# BatteryMainSystem.net
KiCad netlist of a schematic drawn in Altium Designer
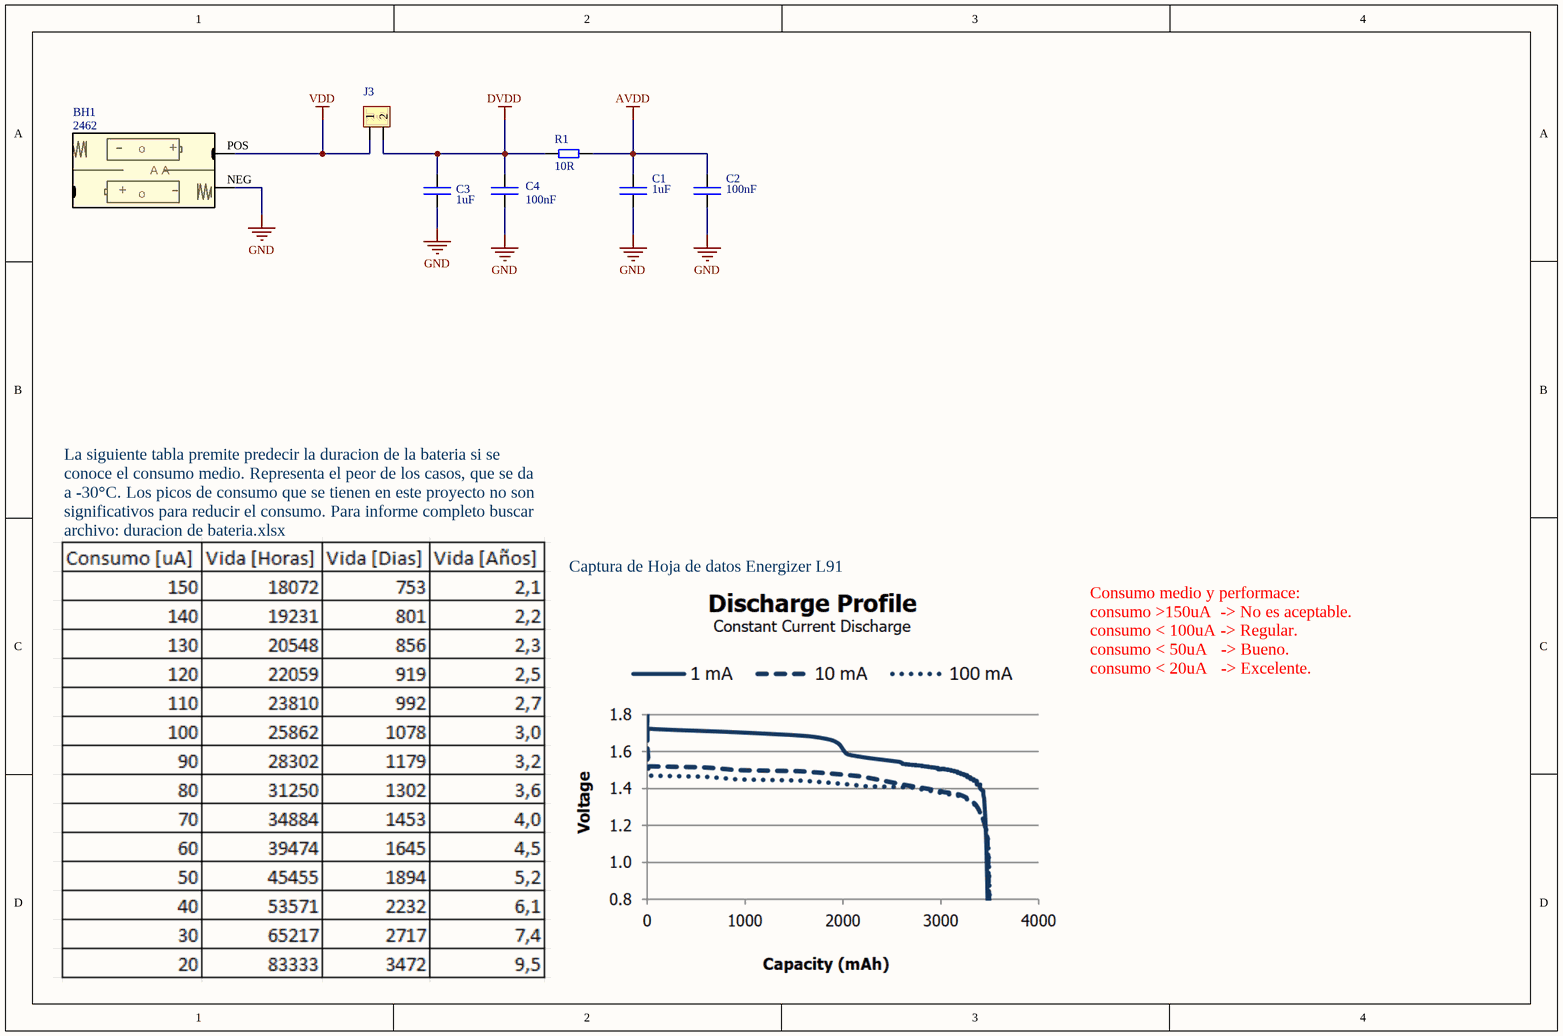
[diagram p0: BatteryMainSystem.SchDoc]

(export (version "E")
  (design (tool "Eeschema 10.0.6"))
  (components
    (comp (ref "BH1")
      (value "2462")
      (footprint "BATTERY_HOLDER_2XAA")
      (description "Battery holder 2XAA TH")
      (fields (field (name "MANUFACTURER") "Keystone"))
      (libsource (lib "flowmeet") (part "2462"))
    )
    (comp (ref "C1")
      (value "1uF")
      (footprint "CAP_SM0603_YAGEOCC2_N")
      (description "CAP 1uF SM0603 X7R 10V YAGEO CC2")
      (fields
        (field (name "MANUFACTURER") "Yageo")
        (field (name "MANUFACTURER PART NUMBER") "CC0603KRX7R6BB105")
      )
      (libsource (lib "yageo") (part "CC0603KRX7R6BB105"))
    )
    (comp (ref "C2")
      (value "100nF")
      (footprint "CAP_SM0603_YAGEOCC2_N")
      (description "CAP 100nF SM0603 X7R 50V YAGEO CC2")
      (fields
        (field (name "MANUFACTURER") "Yageo")
        (field (name "MANUFACTURER PART NUMBER") "CC0603KRX7R9BB104")
      )
      (libsource (lib "yageo") (part "CC0603KRX7R9BB104"))
    )
    (comp (ref "C3")
      (value "1uF")
      (footprint "CAP_SM0603_YAGEOCC2_N")
      (description "CAP 1uF SM0603 X7R 10V YAGEO CC2")
      (fields
        (field (name "MANUFACTURER") "Yageo")
        (field (name "MANUFACTURER PART NUMBER") "CC0603KRX7R6BB105")
      )
      (libsource (lib "yageo") (part "CC0603KRX7R6BB105"))
    )
    (comp (ref "C4")
      (value "100nF")
      (footprint "CAP_SM0603_YAGEOCC2_N")
      (description "CAP 100nF SM0603 X7R 50V YAGEO CC2")
      (fields
        (field (name "MANUFACTURER") "Yageo")
        (field (name "MANUFACTURER PART NUMBER") "CC0603KRX7R9BB104")
      )
      (libsource (lib "yageo") (part "CC0603KRX7R9BB104"))
    )
    (comp (ref "J3")
      (value "54101-T0600LF-CUT-2")
      (footprint "HEADER PIN 1X2")
      (description "Pin header pitch 2.54 TH - cuttable 2 od 36 positions.")
      (fields
        (field (name "MANUFACTURER") "Amphenol ICC")
        (field (name "MANUFACTURER PART NUMBER") "54101-T0600LF")
      )
      (libsource (lib "flowmeet") (part "54101-T0600LF-CUT-2"))
    )
    (comp (ref "R1")
      (value "10R")
      (footprint "RES_SM0603_YAGEORC_N")
      (description "RES 10R SM0603 YAGEO RC_L")
      (fields
        (field (name "MANUFACTURER") "Yageo")
        (field (name "MANUFACTURER PART NUMBER") "RC0603FR-0710RL")
      )
      (libsource (lib "yageo") (part "RC0603FR-0710RL"))
    )
  )
  (nets
    (net (code "1") (name "AVDD") (class "Default")
      (node (ref "C1") (pin "1") (pintype "passive"))
      (node (ref "C2") (pin "1") (pintype "passive"))
      (node (ref "R1") (pin "2") (pintype "passive"))
    )
    (net (code "2") (name "DVDD") (class "Default")
      (node (ref "C3") (pin "1") (pintype "passive"))
      (node (ref "C4") (pin "1") (pintype "passive"))
      (node (ref "J3") (pin "2") (pinfunction "2_2") (pintype "passive"))
      (node (ref "R1") (pin "1") (pintype "passive"))
    )
    (net (code "3") (name "GND") (class "Default")
      (node (ref "BH1") (pin "NEG") (pinfunction "NEG_NEG") (pintype "passive"))
      (node (ref "C1") (pin "2") (pintype "passive"))
      (node (ref "C2") (pin "2") (pintype "passive"))
      (node (ref "C3") (pin "2") (pintype "passive"))
      (node (ref "C4") (pin "2") (pintype "passive"))
    )
    (net (code "4") (name "VDD") (class "Default")
      (node (ref "BH1") (pin "POS") (pinfunction "POS_POS") (pintype "passive"))
      (node (ref "J3") (pin "1") (pinfunction "1_1") (pintype "passive"))
    )
  )
)
